# 32-pin_QFN_TQFP.net
KiCad netlist of a schematic drawn in EAGLE
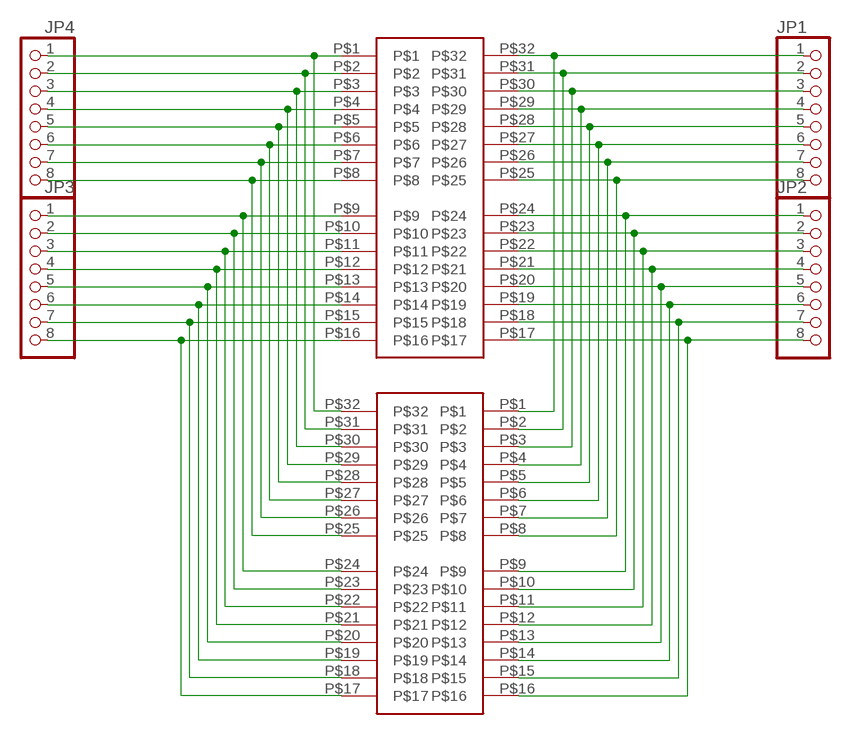
[diagram p0: schematic, sheet 1]

(export (version "E")
  (design (tool "Eeschema 10.0.6"))
  (components
    (comp (ref "JP1")
      (value "PADS-8CLEANBIG")
      (footprint "eagle-import:PADS-8")
      (libsource (lib "eagle-import") (part "PADS-8CLEANBIG"))
    )
    (comp (ref "JP2")
      (value "PADS-8CLEANBIG")
      (footprint "eagle-import:PADS-8")
      (libsource (lib "eagle-import") (part "PADS-8CLEANBIG"))
    )
    (comp (ref "JP3")
      (value "PADS-8CLEANBIG")
      (footprint "eagle-import:PADS-8")
      (libsource (lib "eagle-import") (part "PADS-8CLEANBIG"))
    )
    (comp (ref "JP4")
      (value "PADS-8CLEANBIG")
      (footprint "eagle-import:PADS-8")
      (libsource (lib "eagle-import") (part "PADS-8CLEANBIG"))
    )
    (comp (ref "U$1")
      (value "32-PINQFN")
      (footprint "eagle-import:QFN32")
      (libsource (lib "eagle-import") (part "32-PINQFN"))
    )
    (comp (ref "U$2")
      (value "32-PINTQFP")
      (footprint "eagle-import:TQFP32-08")
      (libsource (lib "eagle-import") (part "32-PINTQFP"))
    )
  )
  (nets
    (net (code "1") (name "Net-(JP1-Pad1)") (class "Default")
      (node (ref "JP1") (pin "1") (pinfunction "1_1") (pintype "passive"))
      (node (ref "U$1") (pin "P$32") (pinfunction "P$32_P$32") (pintype "bidirectional"))
      (node (ref "U$2") (pin "P$1") (pinfunction "P$1_P$1") (pintype "bidirectional"))
    )
    (net (code "2") (name "Net-(JP1-Pad2)") (class "Default")
      (node (ref "JP1") (pin "2") (pinfunction "2_2") (pintype "passive"))
      (node (ref "U$1") (pin "P$31") (pinfunction "P$31_P$31") (pintype "bidirectional"))
      (node (ref "U$2") (pin "P$2") (pinfunction "P$2_P$2") (pintype "bidirectional"))
    )
    (net (code "3") (name "Net-(JP1-Pad3)") (class "Default")
      (node (ref "JP1") (pin "3") (pinfunction "3_3") (pintype "passive"))
      (node (ref "U$1") (pin "P$30") (pinfunction "P$30_P$30") (pintype "bidirectional"))
      (node (ref "U$2") (pin "P$3") (pinfunction "P$3_P$3") (pintype "bidirectional"))
    )
    (net (code "4") (name "Net-(JP1-Pad4)") (class "Default")
      (node (ref "JP1") (pin "4") (pinfunction "4_4") (pintype "passive"))
      (node (ref "U$1") (pin "P$29") (pinfunction "P$29_P$29") (pintype "bidirectional"))
      (node (ref "U$2") (pin "P$4") (pinfunction "P$4_P$4") (pintype "bidirectional"))
    )
    (net (code "5") (name "Net-(JP1-Pad5)") (class "Default")
      (node (ref "JP1") (pin "5") (pinfunction "5_5") (pintype "passive"))
      (node (ref "U$1") (pin "P$28") (pinfunction "P$28_P$28") (pintype "bidirectional"))
      (node (ref "U$2") (pin "P$5") (pinfunction "P$5_P$5") (pintype "bidirectional"))
    )
    (net (code "6") (name "Net-(JP1-Pad6)") (class "Default")
      (node (ref "JP1") (pin "6") (pinfunction "6_6") (pintype "passive"))
      (node (ref "U$1") (pin "P$27") (pinfunction "P$27_P$27") (pintype "bidirectional"))
      (node (ref "U$2") (pin "P$6") (pinfunction "P$6_P$6") (pintype "bidirectional"))
    )
    (net (code "7") (name "Net-(JP1-Pad7)") (class "Default")
      (node (ref "JP1") (pin "7") (pinfunction "7_7") (pintype "passive"))
      (node (ref "U$1") (pin "P$26") (pinfunction "P$26_P$26") (pintype "bidirectional"))
      (node (ref "U$2") (pin "P$7") (pinfunction "P$7_P$7") (pintype "bidirectional"))
    )
    (net (code "8") (name "Net-(JP1-Pad8)") (class "Default")
      (node (ref "JP1") (pin "8") (pinfunction "8_8") (pintype "passive"))
      (node (ref "U$1") (pin "P$25") (pinfunction "P$25_P$25") (pintype "bidirectional"))
      (node (ref "U$2") (pin "P$8") (pinfunction "P$8_P$8") (pintype "bidirectional"))
    )
    (net (code "9") (name "Net-(JP2-Pad1)") (class "Default")
      (node (ref "JP2") (pin "1") (pinfunction "1_1") (pintype "passive"))
      (node (ref "U$1") (pin "P$24") (pinfunction "P$24_P$24") (pintype "bidirectional"))
      (node (ref "U$2") (pin "P$9") (pinfunction "P$9_P$9") (pintype "bidirectional"))
    )
    (net (code "10") (name "Net-(JP2-Pad2)") (class "Default")
      (node (ref "JP2") (pin "2") (pinfunction "2_2") (pintype "passive"))
      (node (ref "U$1") (pin "P$23") (pinfunction "P$23_P$23") (pintype "bidirectional"))
      (node (ref "U$2") (pin "P$10") (pinfunction "P$10_P$10") (pintype "bidirectional"))
    )
    (net (code "11") (name "Net-(JP2-Pad3)") (class "Default")
      (node (ref "JP2") (pin "3") (pinfunction "3_3") (pintype "passive"))
      (node (ref "U$1") (pin "P$22") (pinfunction "P$22_P$22") (pintype "bidirectional"))
      (node (ref "U$2") (pin "P$11") (pinfunction "P$11_P$11") (pintype "bidirectional"))
    )
    (net (code "12") (name "Net-(JP2-Pad4)") (class "Default")
      (node (ref "JP2") (pin "4") (pinfunction "4_4") (pintype "passive"))
      (node (ref "U$1") (pin "P$21") (pinfunction "P$21_P$21") (pintype "bidirectional"))
      (node (ref "U$2") (pin "P$12") (pinfunction "P$12_P$12") (pintype "bidirectional"))
    )
    (net (code "13") (name "Net-(JP2-Pad5)") (class "Default")
      (node (ref "JP2") (pin "5") (pinfunction "5_5") (pintype "passive"))
      (node (ref "U$1") (pin "P$20") (pinfunction "P$20_P$20") (pintype "bidirectional"))
      (node (ref "U$2") (pin "P$13") (pinfunction "P$13_P$13") (pintype "bidirectional"))
    )
    (net (code "14") (name "Net-(JP2-Pad6)") (class "Default")
      (node (ref "JP2") (pin "6") (pinfunction "6_6") (pintype "passive"))
      (node (ref "U$1") (pin "P$19") (pinfunction "P$19_P$19") (pintype "bidirectional"))
      (node (ref "U$2") (pin "P$14") (pinfunction "P$14_P$14") (pintype "bidirectional"))
    )
    (net (code "15") (name "Net-(JP2-Pad7)") (class "Default")
      (node (ref "JP2") (pin "7") (pinfunction "7_7") (pintype "passive"))
      (node (ref "U$1") (pin "P$18") (pinfunction "P$18_P$18") (pintype "bidirectional"))
      (node (ref "U$2") (pin "P$15") (pinfunction "P$15_P$15") (pintype "bidirectional"))
    )
    (net (code "16") (name "Net-(JP2-Pad8)") (class "Default")
      (node (ref "JP2") (pin "8") (pinfunction "8_8") (pintype "passive"))
      (node (ref "U$1") (pin "P$17") (pinfunction "P$17_P$17") (pintype "bidirectional"))
      (node (ref "U$2") (pin "P$16") (pinfunction "P$16_P$16") (pintype "bidirectional"))
    )
    (net (code "17") (name "Net-(JP3-Pad1)") (class "Default")
      (node (ref "JP3") (pin "1") (pinfunction "1_1") (pintype "passive"))
      (node (ref "U$1") (pin "P$9") (pinfunction "P$9_P$9") (pintype "bidirectional"))
      (node (ref "U$2") (pin "P$24") (pinfunction "P$24_P$24") (pintype "bidirectional"))
    )
    (net (code "18") (name "Net-(JP3-Pad2)") (class "Default")
      (node (ref "JP3") (pin "2") (pinfunction "2_2") (pintype "passive"))
      (node (ref "U$1") (pin "P$10") (pinfunction "P$10_P$10") (pintype "bidirectional"))
      (node (ref "U$2") (pin "P$23") (pinfunction "P$23_P$23") (pintype "bidirectional"))
    )
    (net (code "19") (name "Net-(JP3-Pad3)") (class "Default")
      (node (ref "JP3") (pin "3") (pinfunction "3_3") (pintype "passive"))
      (node (ref "U$1") (pin "P$11") (pinfunction "P$11_P$11") (pintype "bidirectional"))
      (node (ref "U$2") (pin "P$22") (pinfunction "P$22_P$22") (pintype "bidirectional"))
    )
    (net (code "20") (name "Net-(JP3-Pad4)") (class "Default")
      (node (ref "JP3") (pin "4") (pinfunction "4_4") (pintype "passive"))
      (node (ref "U$1") (pin "P$12") (pinfunction "P$12_P$12") (pintype "bidirectional"))
      (node (ref "U$2") (pin "P$21") (pinfunction "P$21_P$21") (pintype "bidirectional"))
    )
    (net (code "21") (name "Net-(JP3-Pad5)") (class "Default")
      (node (ref "JP3") (pin "5") (pinfunction "5_5") (pintype "passive"))
      (node (ref "U$1") (pin "P$13") (pinfunction "P$13_P$13") (pintype "bidirectional"))
      (node (ref "U$2") (pin "P$20") (pinfunction "P$20_P$20") (pintype "bidirectional"))
    )
    (net (code "22") (name "Net-(JP3-Pad6)") (class "Default")
      (node (ref "JP3") (pin "6") (pinfunction "6_6") (pintype "passive"))
      (node (ref "U$1") (pin "P$14") (pinfunction "P$14_P$14") (pintype "bidirectional"))
      (node (ref "U$2") (pin "P$19") (pinfunction "P$19_P$19") (pintype "bidirectional"))
    )
    (net (code "23") (name "Net-(JP3-Pad7)") (class "Default")
      (node (ref "JP3") (pin "7") (pinfunction "7_7") (pintype "passive"))
      (node (ref "U$1") (pin "P$15") (pinfunction "P$15_P$15") (pintype "bidirectional"))
      (node (ref "U$2") (pin "P$18") (pinfunction "P$18_P$18") (pintype "bidirectional"))
    )
    (net (code "24") (name "Net-(JP3-Pad8)") (class "Default")
      (node (ref "JP3") (pin "8") (pinfunction "8_8") (pintype "passive"))
      (node (ref "U$1") (pin "P$16") (pinfunction "P$16_P$16") (pintype "bidirectional"))
      (node (ref "U$2") (pin "P$17") (pinfunction "P$17_P$17") (pintype "bidirectional"))
    )
    (net (code "25") (name "Net-(JP4-Pad1)") (class "Default")
      (node (ref "JP4") (pin "1") (pinfunction "1_1") (pintype "passive"))
      (node (ref "U$1") (pin "P$1") (pinfunction "P$1_P$1") (pintype "bidirectional"))
      (node (ref "U$2") (pin "P$32") (pinfunction "P$32_P$32") (pintype "bidirectional"))
    )
    (net (code "26") (name "Net-(JP4-Pad2)") (class "Default")
      (node (ref "JP4") (pin "2") (pinfunction "2_2") (pintype "passive"))
      (node (ref "U$1") (pin "P$2") (pinfunction "P$2_P$2") (pintype "bidirectional"))
      (node (ref "U$2") (pin "P$31") (pinfunction "P$31_P$31") (pintype "bidirectional"))
    )
    (net (code "27") (name "Net-(JP4-Pad3)") (class "Default")
      (node (ref "JP4") (pin "3") (pinfunction "3_3") (pintype "passive"))
      (node (ref "U$1") (pin "P$3") (pinfunction "P$3_P$3") (pintype "bidirectional"))
      (node (ref "U$2") (pin "P$30") (pinfunction "P$30_P$30") (pintype "bidirectional"))
    )
    (net (code "28") (name "Net-(JP4-Pad4)") (class "Default")
      (node (ref "JP4") (pin "4") (pinfunction "4_4") (pintype "passive"))
      (node (ref "U$1") (pin "P$4") (pinfunction "P$4_P$4") (pintype "bidirectional"))
      (node (ref "U$2") (pin "P$29") (pinfunction "P$29_P$29") (pintype "bidirectional"))
    )
    (net (code "29") (name "Net-(JP4-Pad5)") (class "Default")
      (node (ref "JP4") (pin "5") (pinfunction "5_5") (pintype "passive"))
      (node (ref "U$1") (pin "P$5") (pinfunction "P$5_P$5") (pintype "bidirectional"))
      (node (ref "U$2") (pin "P$28") (pinfunction "P$28_P$28") (pintype "bidirectional"))
    )
    (net (code "30") (name "Net-(JP4-Pad6)") (class "Default")
      (node (ref "JP4") (pin "6") (pinfunction "6_6") (pintype "passive"))
      (node (ref "U$1") (pin "P$6") (pinfunction "P$6_P$6") (pintype "bidirectional"))
      (node (ref "U$2") (pin "P$27") (pinfunction "P$27_P$27") (pintype "bidirectional"))
    )
    (net (code "31") (name "Net-(JP4-Pad7)") (class "Default")
      (node (ref "JP4") (pin "7") (pinfunction "7_7") (pintype "passive"))
      (node (ref "U$1") (pin "P$7") (pinfunction "P$7_P$7") (pintype "bidirectional"))
      (node (ref "U$2") (pin "P$26") (pinfunction "P$26_P$26") (pintype "bidirectional"))
    )
    (net (code "32") (name "Net-(JP4-Pad8)") (class "Default")
      (node (ref "JP4") (pin "8") (pinfunction "8_8") (pintype "passive"))
      (node (ref "U$1") (pin "P$8") (pinfunction "P$8_P$8") (pintype "bidirectional"))
      (node (ref "U$2") (pin "P$25") (pinfunction "P$25_P$25") (pintype "bidirectional"))
    )
  )
)
